# marqee_attiny85.net
KiCad netlist of a schematic drawn in EAGLE
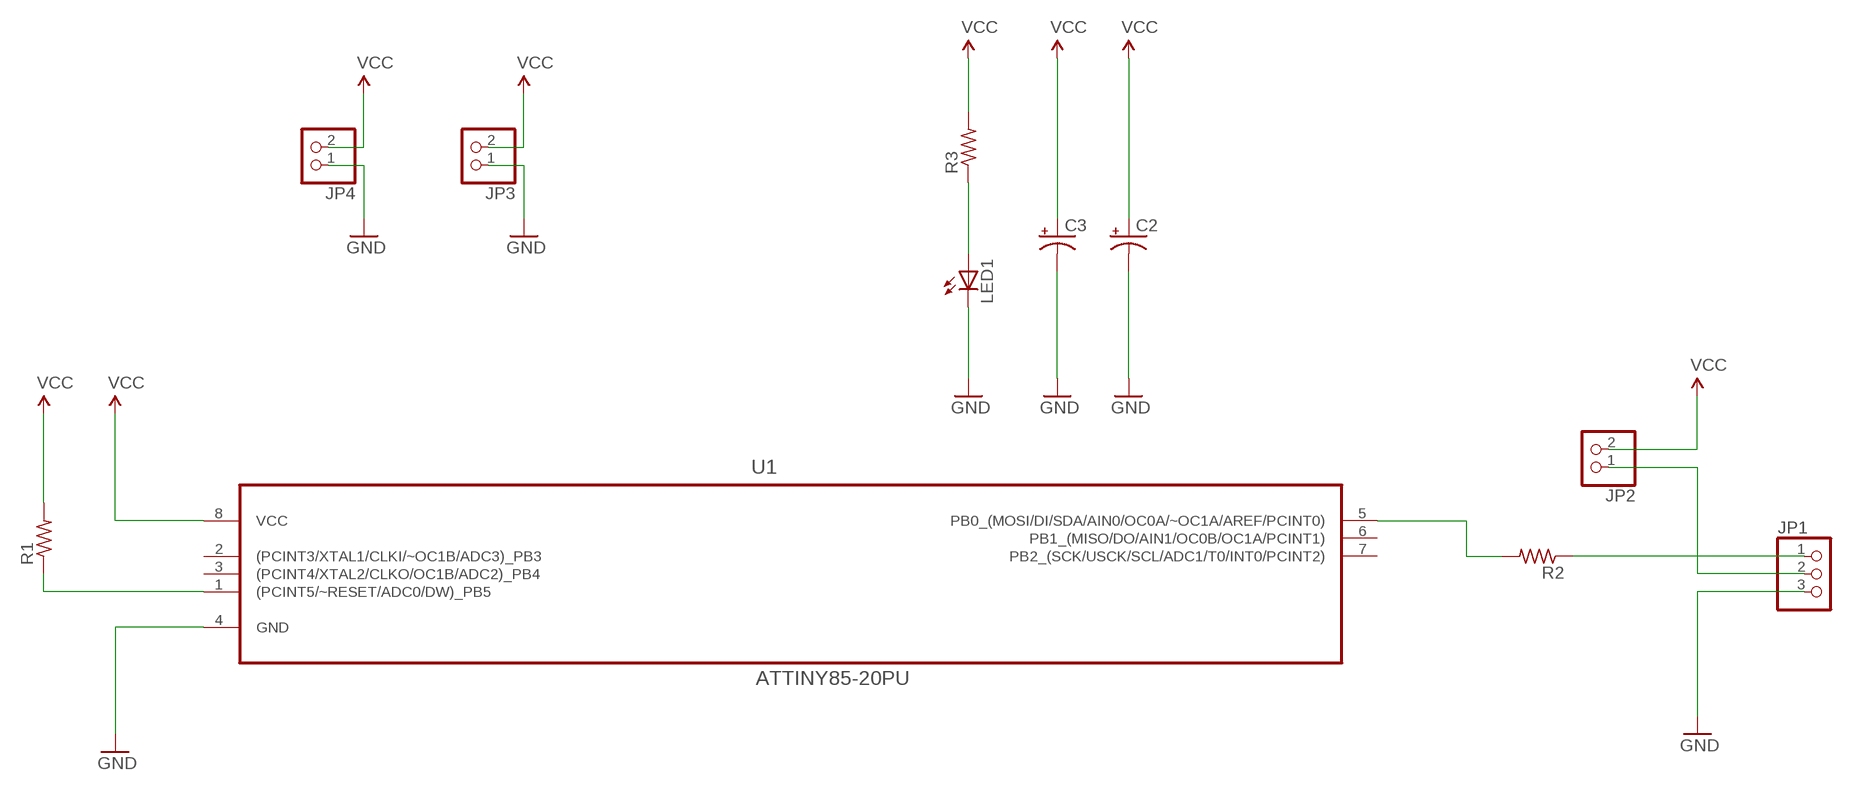
[diagram p0: schematic, sheet 1]

(export (version "E")
  (design (tool "Eeschema 10.0.6"))
  (components
    (comp (ref "C2")
      (value "CPOL-USE5-8.5")
      (footprint "eagle-import:E5-8,5")
      (libsource (lib "eagle-import") (part "CPOL-USE5-8.5"))
    )
    (comp (ref "C3")
      (value "CPOL-USE5-8.5")
      (footprint "eagle-import:E5-8,5")
      (libsource (lib "eagle-import") (part "CPOL-USE5-8.5"))
    )
    (comp (ref "JP1")
      (value "PINHD-1X3")
      (footprint "eagle-import:1X03")
      (libsource (lib "eagle-import") (part "PINHD-1X3"))
    )
    (comp (ref "JP2")
      (value "PINHD-1X2")
      (footprint "eagle-import:1X02")
      (libsource (lib "eagle-import") (part "PINHD-1X2"))
    )
    (comp (ref "JP3")
      (value "PINHD-1X2")
      (footprint "eagle-import:1X02")
      (libsource (lib "eagle-import") (part "PINHD-1X2"))
    )
    (comp (ref "JP4")
      (value "PINHD-1X2")
      (footprint "eagle-import:1X02")
      (libsource (lib "eagle-import") (part "PINHD-1X2"))
    )
    (comp (ref "LED1")
      (value "LED5MM")
      (footprint "eagle-import:LED5MM")
      (libsource (lib "eagle-import") (part "LED5MM"))
    )
    (comp (ref "R1")
      (value "R-US_0207/10")
      (footprint "eagle-import:0207_10")
      (libsource (lib "eagle-import") (part "R-US_0207/10"))
    )
    (comp (ref "R2")
      (value "R-US_0207/10")
      (footprint "eagle-import:0207_10")
      (libsource (lib "eagle-import") (part "R-US_0207/10"))
    )
    (comp (ref "R3")
      (value "R-US_0207/10")
      (footprint "eagle-import:0207_10")
      (libsource (lib "eagle-import") (part "R-US_0207/10"))
    )
    (comp (ref "U1")
      (value "ATTINY85-20PU")
      (footprint "eagle-import:DIP254P762X533-8")
      (libsource (lib "eagle-import") (part "ATTINY85-20PU"))
    )
  )
  (nets
    (net (code "1") (name "GND") (class "Default")
      (node (ref "C2") (pin "-") (pinfunction "-_-") (pintype "passive"))
      (node (ref "C3") (pin "-") (pinfunction "-_-") (pintype "passive"))
      (node (ref "JP1") (pin "3") (pinfunction "3_3") (pintype "passive"))
      (node (ref "JP3") (pin "1") (pinfunction "1_1") (pintype "passive"))
      (node (ref "JP4") (pin "1") (pinfunction "1_1") (pintype "passive"))
      (node (ref "LED1") (pin "K") (pinfunction "C_K") (pintype "passive"))
      (node (ref "U1") (pin "4") (pinfunction "GND_4") (pintype "passive"))
    )
    (net (code "2") (name "Net-(JP1-Pad1)") (class "Default")
      (node (ref "JP1") (pin "1") (pinfunction "1_1") (pintype "passive"))
      (node (ref "R2") (pin "1") (pinfunction "1_1") (pintype "passive"))
    )
    (net (code "3") (name "Net-(JP1-Pad2)") (class "Default")
      (node (ref "JP1") (pin "2") (pinfunction "2_2") (pintype "passive"))
      (node (ref "JP2") (pin "1") (pinfunction "1_1") (pintype "passive"))
    )
    (net (code "4") (name "Net-(LED1-PadA)") (class "Default")
      (node (ref "LED1") (pin "A") (pinfunction "A_A") (pintype "passive"))
      (node (ref "R3") (pin "1") (pinfunction "1_1") (pintype "passive"))
    )
    (net (code "5") (name "Net-(U1-(PCINT5{slash}~{RESET{slash}ADC0{slash}DW})_PB5)") (class "Default")
      (node (ref "R1") (pin "1") (pinfunction "1_1") (pintype "passive"))
      (node (ref "U1") (pin "1") (pinfunction "(PCINT5/~{RESET/ADC0/DW})_PB5_1") (pintype "bidirectional"))
    )
    (net (code "6") (name "Net-(U1-PB0_(MOSI{slash}DI{slash}SDA{slash}AIN0{slash}OC0A{slash}~{OC1A{slash}AREF{slash}PCINT0}))") (class "Default")
      (node (ref "R2") (pin "2") (pinfunction "2_2") (pintype "passive"))
      (node (ref "U1") (pin "5") (pinfunction "PB0_(MOSI/DI/SDA/AIN0/OC0A/~{OC1A/AREF/PCINT0})_5") (pintype "bidirectional"))
    )
    (net (code "7") (name "VCC") (class "Default")
      (node (ref "C2") (pin "+") (pinfunction "+_+") (pintype "passive"))
      (node (ref "C3") (pin "+") (pinfunction "+_+") (pintype "passive"))
      (node (ref "JP2") (pin "2") (pinfunction "2_2") (pintype "passive"))
      (node (ref "JP3") (pin "2") (pinfunction "2_2") (pintype "passive"))
      (node (ref "JP4") (pin "2") (pinfunction "2_2") (pintype "passive"))
      (node (ref "R1") (pin "2") (pinfunction "2_2") (pintype "passive"))
      (node (ref "R3") (pin "2") (pinfunction "2_2") (pintype "passive"))
      (node (ref "U1") (pin "8") (pinfunction "VCC_8") (pintype "power_in"))
    )
    (net (code "8") (name "unconnected-(U1-(PCINT3{slash}XTAL1{slash}CLKI{slash}~{OC1B{slash}ADC3})_PB3-Pad2)") (class "Default")
      (node (ref "U1") (pin "2") (pinfunction "(PCINT3/XTAL1/CLKI/~{OC1B/ADC3})_PB3_2") (pintype "bidirectional"))
    )
    (net (code "9") (name "unconnected-(U1-(PCINT4{slash}XTAL2{slash}CLKO{slash}OC1B{slash}ADC2)_PB4-Pad3)") (class "Default")
      (node (ref "U1") (pin "3") (pinfunction "(PCINT4/XTAL2/CLKO/OC1B/ADC2)_PB4_3") (pintype "bidirectional"))
    )
    (net (code "10") (name "unconnected-(U1-PB1_(MISO{slash}DO{slash}AIN1{slash}OC0B{slash}OC1A{slash}PCINT1)-Pad6)") (class "Default")
      (node (ref "U1") (pin "6") (pinfunction "PB1_(MISO/DO/AIN1/OC0B/OC1A/PCINT1)_6") (pintype "bidirectional"))
    )
    (net (code "11") (name "unconnected-(U1-PB2_(SCK{slash}USCK{slash}SCL{slash}ADC1{slash}T0{slash}INT0{slash}PCINT2)-Pad7)") (class "Default")
      (node (ref "U1") (pin "7") (pinfunction "PB2_(SCK/USCK/SCL/ADC1/T0/INT0/PCINT2)_7") (pintype "bidirectional"))
    )
  )
)
